# SCH_beushed-esc_2025-11-09.net
KiCad netlist of a schematic drawn in EasyEDA
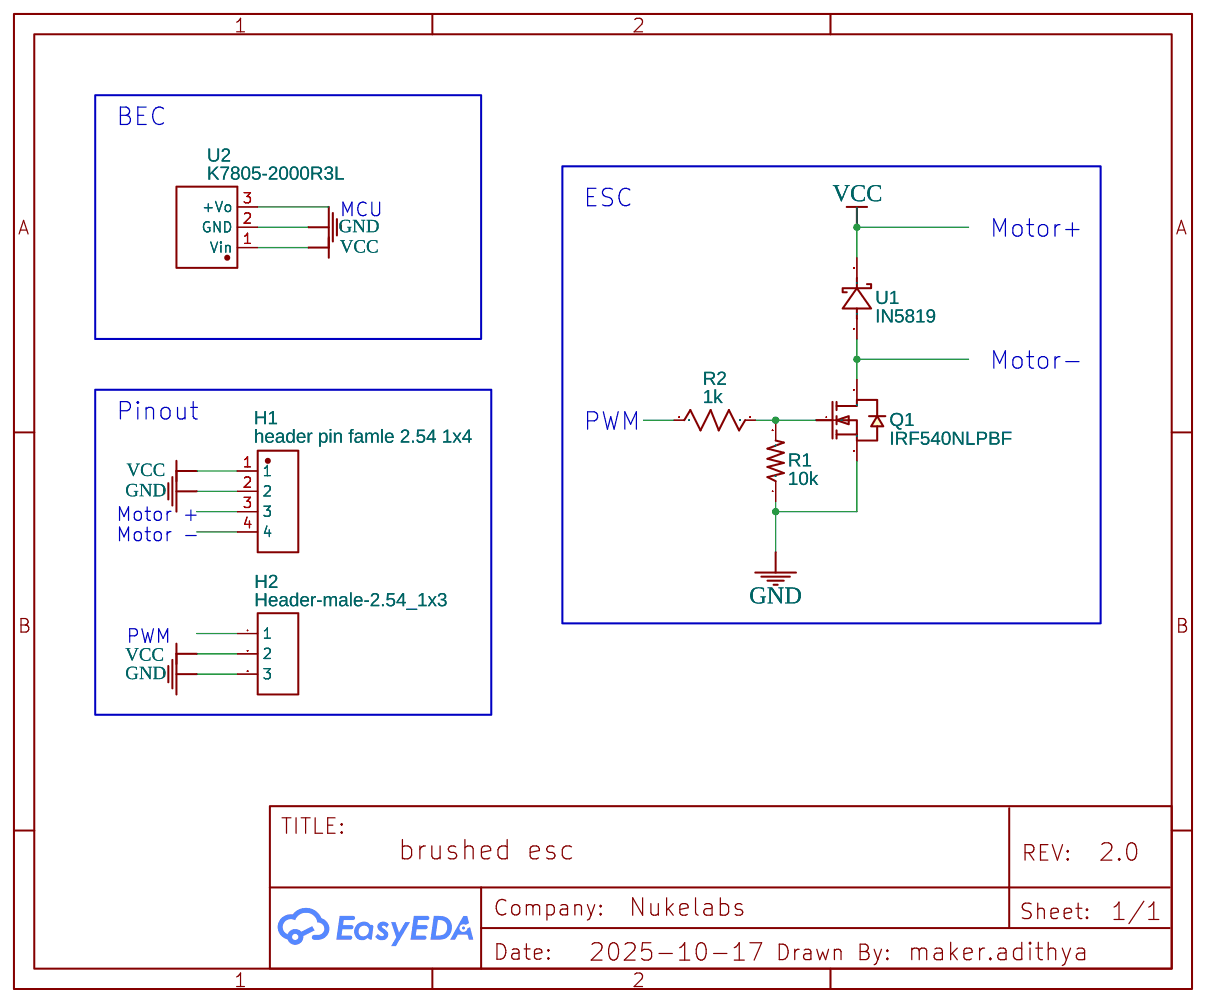
[diagram p0: schematic sheet]

(export (version "E")
  (design (tool "Eeschema 10.0.6"))
  (components
    (comp (ref "H1")
      (value "header pin famle 2.54 1x4")
      (fields
        (field (name "Manufacturer Part") "HX PH254-01-04-Z-L11.5 straight pin header")
        (field (name "Manufacturer") "hanxia(韩下)")
      )
      (libsource (lib "") (part "HX PH254-01-04-Z-L11.5 STRAIGHT PIN HEADER"))
    )
    (comp (ref "H2")
      (value "Header-male-2.54_1x3")
      (fields (field (name "Manufacturer Part") "2.54-1*3P母") (field (name "Manufacturer") "BOOMELE(博穆精密)"))
      (libsource (lib "") (part "Header-Female-2.54_1x3"))
    )
    (comp (ref "Q1")
      (value "IRF540NLPBF")
      (fields (field (name "Manufacturer") "Infineon(英飞凌)"))
      (libsource (lib "") (part "IRF540NLPBF"))
    )
    (comp (ref "R1") (value "10k") (libsource (lib "") (part "RESISTOR copy")))
    (comp (ref "R2") (value "1k") (libsource (lib "") (part "R_0603_US")))
    (comp (ref "U1") (value "IN5819") (libsource (lib "") (part "IN5819")))
    (comp (ref "U2")
      (value "K7805-2000R3L")
      (fields (field (name "Manufacturer") "MORNSUN(金升阳)"))
      (libsource (lib "") (part "K7805-2000R3L"))
    )
  )
  (nets
    (net (code "1") (name "GND") (class "Default")
      (node (ref "H1") (pin "2") (pinfunction "2_2") (pintype "unspecified"))
      (node (ref "H2") (pin "3") (pinfunction "3_3") (pintype "input"))
      (node (ref "Q1") (pin "3") (pinfunction "S_3") (pintype "unspecified"))
      (node (ref "R1") (pin "1") (pinfunction "1_1") (pintype "unspecified"))
      (node (ref "U2") (pin "2") (pinfunction "GND_2") (pintype "unspecified"))
    )
    (net (code "2") (name "Net-(Q1-D)") (class "Default")
      (node (ref "Q1") (pin "2") (pinfunction "D_2") (pintype "unspecified"))
      (node (ref "U1") (pin "1") (pinfunction "A_1") (pintype "unspecified"))
    )
    (net (code "3") (name "Net-(Q1-G)") (class "Default")
      (node (ref "Q1") (pin "1") (pinfunction "G_1") (pintype "unspecified"))
      (node (ref "R1") (pin "2") (pinfunction "2_2") (pintype "unspecified"))
      (node (ref "R2") (pin "2") (pinfunction "2_2") (pintype "unspecified"))
    )
    (net (code "4") (name "VCC") (class "Default")
      (node (ref "H1") (pin "1") (pinfunction "1_1") (pintype "unspecified"))
      (node (ref "H2") (pin "2") (pinfunction "2_2") (pintype "input"))
      (node (ref "U1") (pin "2") (pinfunction "K_2") (pintype "unspecified"))
      (node (ref "U2") (pin "1") (pinfunction "Vin_1") (pintype "unspecified"))
    )
    (net (code "5") (name "unconnected-(H1-Pad3)") (class "Default")
      (node (ref "H1") (pin "3") (pinfunction "3_3") (pintype "unspecified"))
    )
    (net (code "6") (name "unconnected-(H1-Pad4)") (class "Default")
      (node (ref "H1") (pin "4") (pinfunction "4_4") (pintype "unspecified"))
    )
    (net (code "7") (name "unconnected-(H2-Pad1)") (class "Default")
      (node (ref "H2") (pin "1") (pinfunction "1_1") (pintype "input"))
    )
    (net (code "8") (name "unconnected-(R2-Pad1)") (class "Default")
      (node (ref "R2") (pin "1") (pinfunction "1_1") (pintype "unspecified"))
    )
    (net (code "9") (name "unconnected-(U2-+Vo-Pad3)") (class "Default")
      (node (ref "U2") (pin "3") (pinfunction "+Vo_3") (pintype "unspecified"))
    )
  )
)
